# BLE_PP_v16.net
KiCad netlist of a schematic drawn in EAGLE
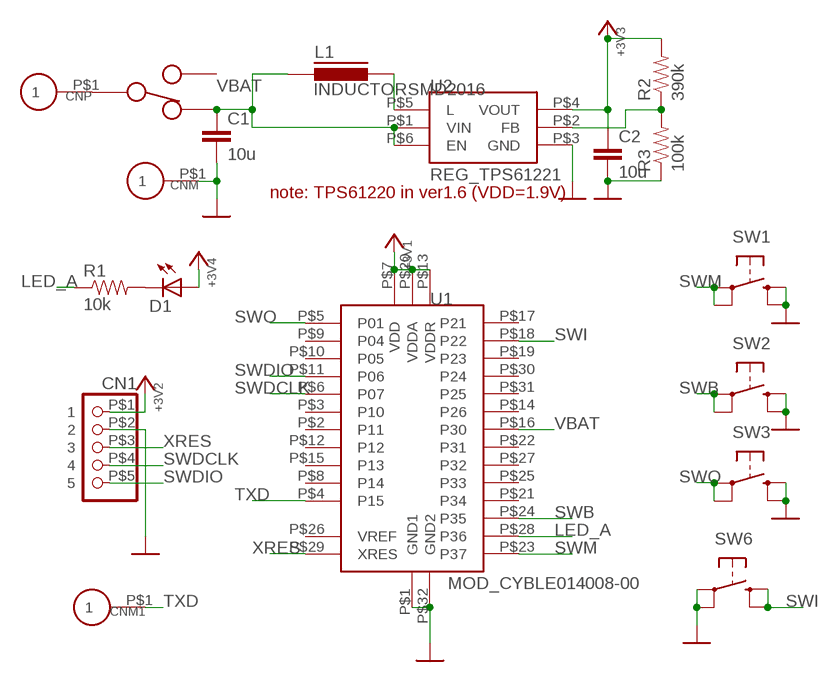
[diagram p0: schematic, sheet 1]

(export (version "E")
  (design (tool "Eeschema 10.0.6"))
  (components
    (comp (ref "C1")
      (value "10u")
      (footprint "eagle-import:0603")
      (libsource (lib "eagle-import") (part "CAP0603"))
    )
    (comp (ref "C2")
      (value "10u")
      (footprint "eagle-import:0603")
      (libsource (lib "eagle-import") (part "CAP0603"))
    )
    (comp (ref "CN1")
      (value "CON_PINHD-1X550MIL")
      (footprint "eagle-import:1X5_50MIL")
      (libsource (lib "eagle-import") (part "CON_PINHD-1X550MIL"))
    )
    (comp (ref "CNM")
      (value "CON_P01SMD1MM")
      (footprint "eagle-import:PAD_SMD1MM")
      (libsource (lib "eagle-import") (part "CON_P01SMD1MM"))
    )
    (comp (ref "CNM1")
      (value "CON_P01SMD1MM")
      (footprint "eagle-import:PAD_SMD1MM")
      (libsource (lib "eagle-import") (part "CON_P01SMD1MM"))
    )
    (comp (ref "CNP")
      (value "CON_P01SMD1MM")
      (footprint "eagle-import:PAD_SMD1MM")
      (libsource (lib "eagle-import") (part "CON_P01SMD1MM"))
    )
    (comp (ref "D1")
      (value "LED0603")
      (footprint "eagle-import:SPARKFUN_LED-0603")
      (libsource (lib "eagle-import") (part "LED0603"))
    )
    (comp (ref "L1")
      (value "INDUCTORSMD2016")
      (footprint "eagle-import:2016")
      (libsource (lib "eagle-import") (part "INDUCTORSMD2016"))
    )
    (comp (ref "R1")
      (value "10k")
      (footprint "eagle-import:0603")
      (libsource (lib "eagle-import") (part "RES0603"))
    )
    (comp (ref "R2")
      (value "390k")
      (footprint "eagle-import:0603")
      (libsource (lib "eagle-import") (part "RES0603"))
    )
    (comp (ref "R3")
      (value "100k")
      (footprint "eagle-import:0603")
      (libsource (lib "eagle-import") (part "RES0603"))
    )
    (comp (ref "SW1")
      (value "SW_TACTEVQP2")
      (footprint "eagle-import:SW_EVQP2")
      (libsource (lib "eagle-import") (part "SW_TACTEVQP2"))
    )
    (comp (ref "SW2")
      (value "SW_TACTEVQPLNA08NOGND")
      (footprint "eagle-import:SW_EVQPLBA08_NOGND")
      (libsource (lib "eagle-import") (part "SW_TACTEVQPLNA08NOGND"))
    )
    (comp (ref "SW3")
      (value "SW_TACTEVQPLNA08NOGND")
      (footprint "eagle-import:SW_EVQPLBA08_NOGND")
      (libsource (lib "eagle-import") (part "SW_TACTEVQPLNA08NOGND"))
    )
    (comp (ref "SW4")
      (value "SW_SLIDECUS12B")
      (footprint "eagle-import:SW_CUS-12B")
      (libsource (lib "eagle-import") (part "SW_SLIDECUS12B"))
    )
    (comp (ref "SW6")
      (value "SW_TACTEVQP7")
      (footprint "eagle-import:SW_EVQP7")
      (libsource (lib "eagle-import") (part "SW_TACTEVQP7"))
    )
    (comp (ref "U1")
      (value "MOD_CYBLE014008-00")
      (footprint "eagle-import:MOD_CYBLE014008-00")
      (libsource (lib "eagle-import") (part "MOD_CYBLE014008-00"))
    )
    (comp (ref "U2")
      (value "REG_TPS61221")
      (footprint "eagle-import:SC70-6")
      (libsource (lib "eagle-import") (part "REG_TPS61221"))
    )
  )
  (nets
    (net (code "1") (name "/LED_A") (class "Default")
      (node (ref "R1") (pin "1") (pinfunction "1_1") (pintype "passive"))
      (node (ref "U1") (pin "P$28") (pinfunction "P36_P$28") (pintype "bidirectional"))
    )
    (net (code "2") (name "/P$3") (class "Default")
      (node (ref "SW4") (pin "P$3") (pinfunction "P$3_P$3") (pintype "power_in"))
    )
    (net (code "3") (name "/SWB") (class "Default")
      (node (ref "SW2") (pin "A1") (pinfunction "P_A1") (pintype "passive"))
      (node (ref "SW2") (pin "A2") (pinfunction "P1_A2") (pintype "passive"))
      (node (ref "U1") (pin "P$24") (pinfunction "P35_P$24") (pintype "bidirectional"))
    )
    (net (code "4") (name "/SWDCLK") (class "Default")
      (node (ref "CN1") (pin "P$4") (pinfunction "4_P$4") (pintype "passive"))
      (node (ref "U1") (pin "P$6") (pinfunction "P07_P$6") (pintype "bidirectional"))
    )
    (net (code "5") (name "/SWDIO") (class "Default")
      (node (ref "CN1") (pin "P$5") (pinfunction "5_P$5") (pintype "passive"))
      (node (ref "U1") (pin "P$11") (pinfunction "P06_P$11") (pintype "bidirectional"))
    )
    (net (code "6") (name "/SWI") (class "Default")
      (node (ref "SW6") (pin "P$2A") (pinfunction "S_P$2A") (pintype "passive"))
      (node (ref "SW6") (pin "P$2B") (pinfunction "S1_P$2B") (pintype "passive"))
      (node (ref "U1") (pin "P$18") (pinfunction "P22_P$18") (pintype "bidirectional"))
    )
    (net (code "7") (name "/SWM") (class "Default")
      (node (ref "SW1") (pin "PA1") (pinfunction "P_PA1") (pintype "passive"))
      (node (ref "SW1") (pin "PA2") (pinfunction "P1_PA2") (pintype "passive"))
      (node (ref "U1") (pin "P$23") (pinfunction "P37_P$23") (pintype "bidirectional"))
    )
    (net (code "8") (name "/SWO") (class "Default")
      (node (ref "SW3") (pin "A1") (pinfunction "P_A1") (pintype "passive"))
      (node (ref "SW3") (pin "A2") (pinfunction "P1_A2") (pintype "passive"))
      (node (ref "U1") (pin "P$5") (pinfunction "P01_P$5") (pintype "bidirectional"))
    )
    (net (code "9") (name "/TXD") (class "Default")
      (node (ref "CNM1") (pin "P$1") (pinfunction "1_P$1") (pintype "bidirectional"))
      (node (ref "U1") (pin "P$4") (pinfunction "P15_P$4") (pintype "bidirectional"))
    )
    (net (code "10") (name "/VBAT") (class "Default")
      (node (ref "C1") (pin "1") (pinfunction "1_1") (pintype "passive"))
      (node (ref "L1") (pin "P$1") (pinfunction "1_P$1") (pintype "passive"))
      (node (ref "SW4") (pin "P$1") (pinfunction "P$1_P$1") (pintype "power_in"))
      (node (ref "U1") (pin "P$16") (pinfunction "P30_P$16") (pintype "bidirectional"))
      (node (ref "U2") (pin "P$1") (pinfunction "VIN_P$1") (pintype "bidirectional"))
      (node (ref "U2") (pin "P$6") (pinfunction "EN_P$6") (pintype "bidirectional"))
    )
    (net (code "11") (name "/XRES") (class "Default")
      (node (ref "CN1") (pin "P$3") (pinfunction "3_P$3") (pintype "passive"))
      (node (ref "U1") (pin "P$29") (pinfunction "XRES_P$29") (pintype "bidirectional"))
    )
    (net (code "12") (name "Net-(CNP-1)") (class "Default")
      (node (ref "CNP") (pin "P$1") (pinfunction "1_P$1") (pintype "bidirectional"))
      (node (ref "SW4") (pin "P$2") (pinfunction "P$2_P$2") (pintype "power_in"))
    )
    (net (code "13") (name "Net-(D1-PadC)") (class "Default")
      (node (ref "D1") (pin "C") (pinfunction "C_C") (pintype "passive"))
      (node (ref "R1") (pin "2") (pinfunction "2_2") (pintype "passive"))
    )
    (net (code "14") (name "Net-(L1-2)") (class "Default")
      (node (ref "L1") (pin "P$2") (pinfunction "2_P$2") (pintype "passive"))
      (node (ref "U2") (pin "P$5") (pinfunction "L_P$5") (pintype "bidirectional"))
    )
    (net (code "15") (name "Net-(U2-FB)") (class "Default")
      (node (ref "R2") (pin "1") (pinfunction "1_1") (pintype "passive"))
      (node (ref "R3") (pin "2") (pinfunction "2_2") (pintype "passive"))
      (node (ref "U2") (pin "P$2") (pinfunction "FB_P$2") (pintype "bidirectional"))
    )
    (net (code "16") (name "POW_+3V3") (class "Default")
      (node (ref "C2") (pin "1") (pinfunction "1_1") (pintype "passive"))
      (node (ref "CN1") (pin "P$1") (pinfunction "1_P$1") (pintype "passive"))
      (node (ref "D1") (pin "A") (pinfunction "A_A") (pintype "passive"))
      (node (ref "R2") (pin "2") (pinfunction "2_2") (pintype "passive"))
      (node (ref "U1") (pin "P$13") (pinfunction "VDDR_P$13") (pintype "bidirectional"))
      (node (ref "U1") (pin "P$20") (pinfunction "VDDA_P$20") (pintype "bidirectional"))
      (node (ref "U1") (pin "P$7") (pinfunction "VDD_P$7") (pintype "bidirectional"))
      (node (ref "U2") (pin "P$4") (pinfunction "VOUT_P$4") (pintype "bidirectional"))
    )
    (net (code "17") (name "POW_GND") (class "Default")
      (node (ref "C1") (pin "2") (pinfunction "2_2") (pintype "passive"))
      (node (ref "C2") (pin "2") (pinfunction "2_2") (pintype "passive"))
      (node (ref "CN1") (pin "P$2") (pinfunction "2_P$2") (pintype "passive"))
      (node (ref "CNM") (pin "P$1") (pinfunction "1_P$1") (pintype "bidirectional"))
      (node (ref "R3") (pin "1") (pinfunction "1_1") (pintype "passive"))
      (node (ref "SW1") (pin "PB1") (pinfunction "S_PB1") (pintype "passive"))
      (node (ref "SW1") (pin "PB2") (pinfunction "S1_PB2") (pintype "passive"))
      (node (ref "SW2") (pin "B1") (pinfunction "S_B1") (pintype "passive"))
      (node (ref "SW2") (pin "B2") (pinfunction "S1_B2") (pintype "passive"))
      (node (ref "SW3") (pin "B1") (pinfunction "S_B1") (pintype "passive"))
      (node (ref "SW3") (pin "B2") (pinfunction "S1_B2") (pintype "passive"))
      (node (ref "SW6") (pin "P$1A") (pinfunction "P_P$1A") (pintype "passive"))
      (node (ref "SW6") (pin "P$1B") (pinfunction "P1_P$1B") (pintype "passive"))
      (node (ref "U1") (pin "P$1") (pinfunction "GND1_P$1") (pintype "bidirectional"))
      (node (ref "U1") (pin "P$32") (pinfunction "GND2_P$32") (pintype "bidirectional"))
      (node (ref "U2") (pin "P$3") (pinfunction "GND_P$3") (pintype "bidirectional"))
    )
    (net (code "18") (name "unconnected-(U1-P04-PadP$9)") (class "Default")
      (node (ref "U1") (pin "P$9") (pinfunction "P04_P$9") (pintype "bidirectional"))
    )
    (net (code "19") (name "unconnected-(U1-P05-PadP$10)") (class "Default")
      (node (ref "U1") (pin "P$10") (pinfunction "P05_P$10") (pintype "bidirectional"))
    )
    (net (code "20") (name "unconnected-(U1-P10-PadP$3)") (class "Default")
      (node (ref "U1") (pin "P$3") (pinfunction "P10_P$3") (pintype "bidirectional"))
    )
    (net (code "21") (name "unconnected-(U1-P11-PadP$2)") (class "Default")
      (node (ref "U1") (pin "P$2") (pinfunction "P11_P$2") (pintype "bidirectional"))
    )
    (net (code "22") (name "unconnected-(U1-P12-PadP$12)") (class "Default")
      (node (ref "U1") (pin "P$12") (pinfunction "P12_P$12") (pintype "bidirectional"))
    )
    (net (code "23") (name "unconnected-(U1-P13-PadP$15)") (class "Default")
      (node (ref "U1") (pin "P$15") (pinfunction "P13_P$15") (pintype "bidirectional"))
    )
    (net (code "24") (name "unconnected-(U1-P14-PadP$8)") (class "Default")
      (node (ref "U1") (pin "P$8") (pinfunction "P14_P$8") (pintype "bidirectional"))
    )
    (net (code "25") (name "unconnected-(U1-P21-PadP$17)") (class "Default")
      (node (ref "U1") (pin "P$17") (pinfunction "P21_P$17") (pintype "bidirectional"))
    )
    (net (code "26") (name "unconnected-(U1-P23-PadP$19)") (class "Default")
      (node (ref "U1") (pin "P$19") (pinfunction "P23_P$19") (pintype "bidirectional"))
    )
    (net (code "27") (name "unconnected-(U1-P24-PadP$30)") (class "Default")
      (node (ref "U1") (pin "P$30") (pinfunction "P24_P$30") (pintype "bidirectional"))
    )
    (net (code "28") (name "unconnected-(U1-P25-PadP$31)") (class "Default")
      (node (ref "U1") (pin "P$31") (pinfunction "P25_P$31") (pintype "bidirectional"))
    )
    (net (code "29") (name "unconnected-(U1-P26-PadP$14)") (class "Default")
      (node (ref "U1") (pin "P$14") (pinfunction "P26_P$14") (pintype "bidirectional"))
    )
    (net (code "30") (name "unconnected-(U1-P31-PadP$22)") (class "Default")
      (node (ref "U1") (pin "P$22") (pinfunction "P31_P$22") (pintype "bidirectional"))
    )
    (net (code "31") (name "unconnected-(U1-P32-PadP$27)") (class "Default")
      (node (ref "U1") (pin "P$27") (pinfunction "P32_P$27") (pintype "bidirectional"))
    )
    (net (code "32") (name "unconnected-(U1-P33-PadP$25)") (class "Default")
      (node (ref "U1") (pin "P$25") (pinfunction "P33_P$25") (pintype "bidirectional"))
    )
    (net (code "33") (name "unconnected-(U1-P34-PadP$21)") (class "Default")
      (node (ref "U1") (pin "P$21") (pinfunction "P34_P$21") (pintype "bidirectional"))
    )
    (net (code "34") (name "unconnected-(U1-VREF-PadP$26)") (class "Default")
      (node (ref "U1") (pin "P$26") (pinfunction "VREF_P$26") (pintype "bidirectional"))
    )
  )
)
